# Si5351_STEMMA_QT_Schematic.net
KiCad netlist of a schematic drawn in EAGLE
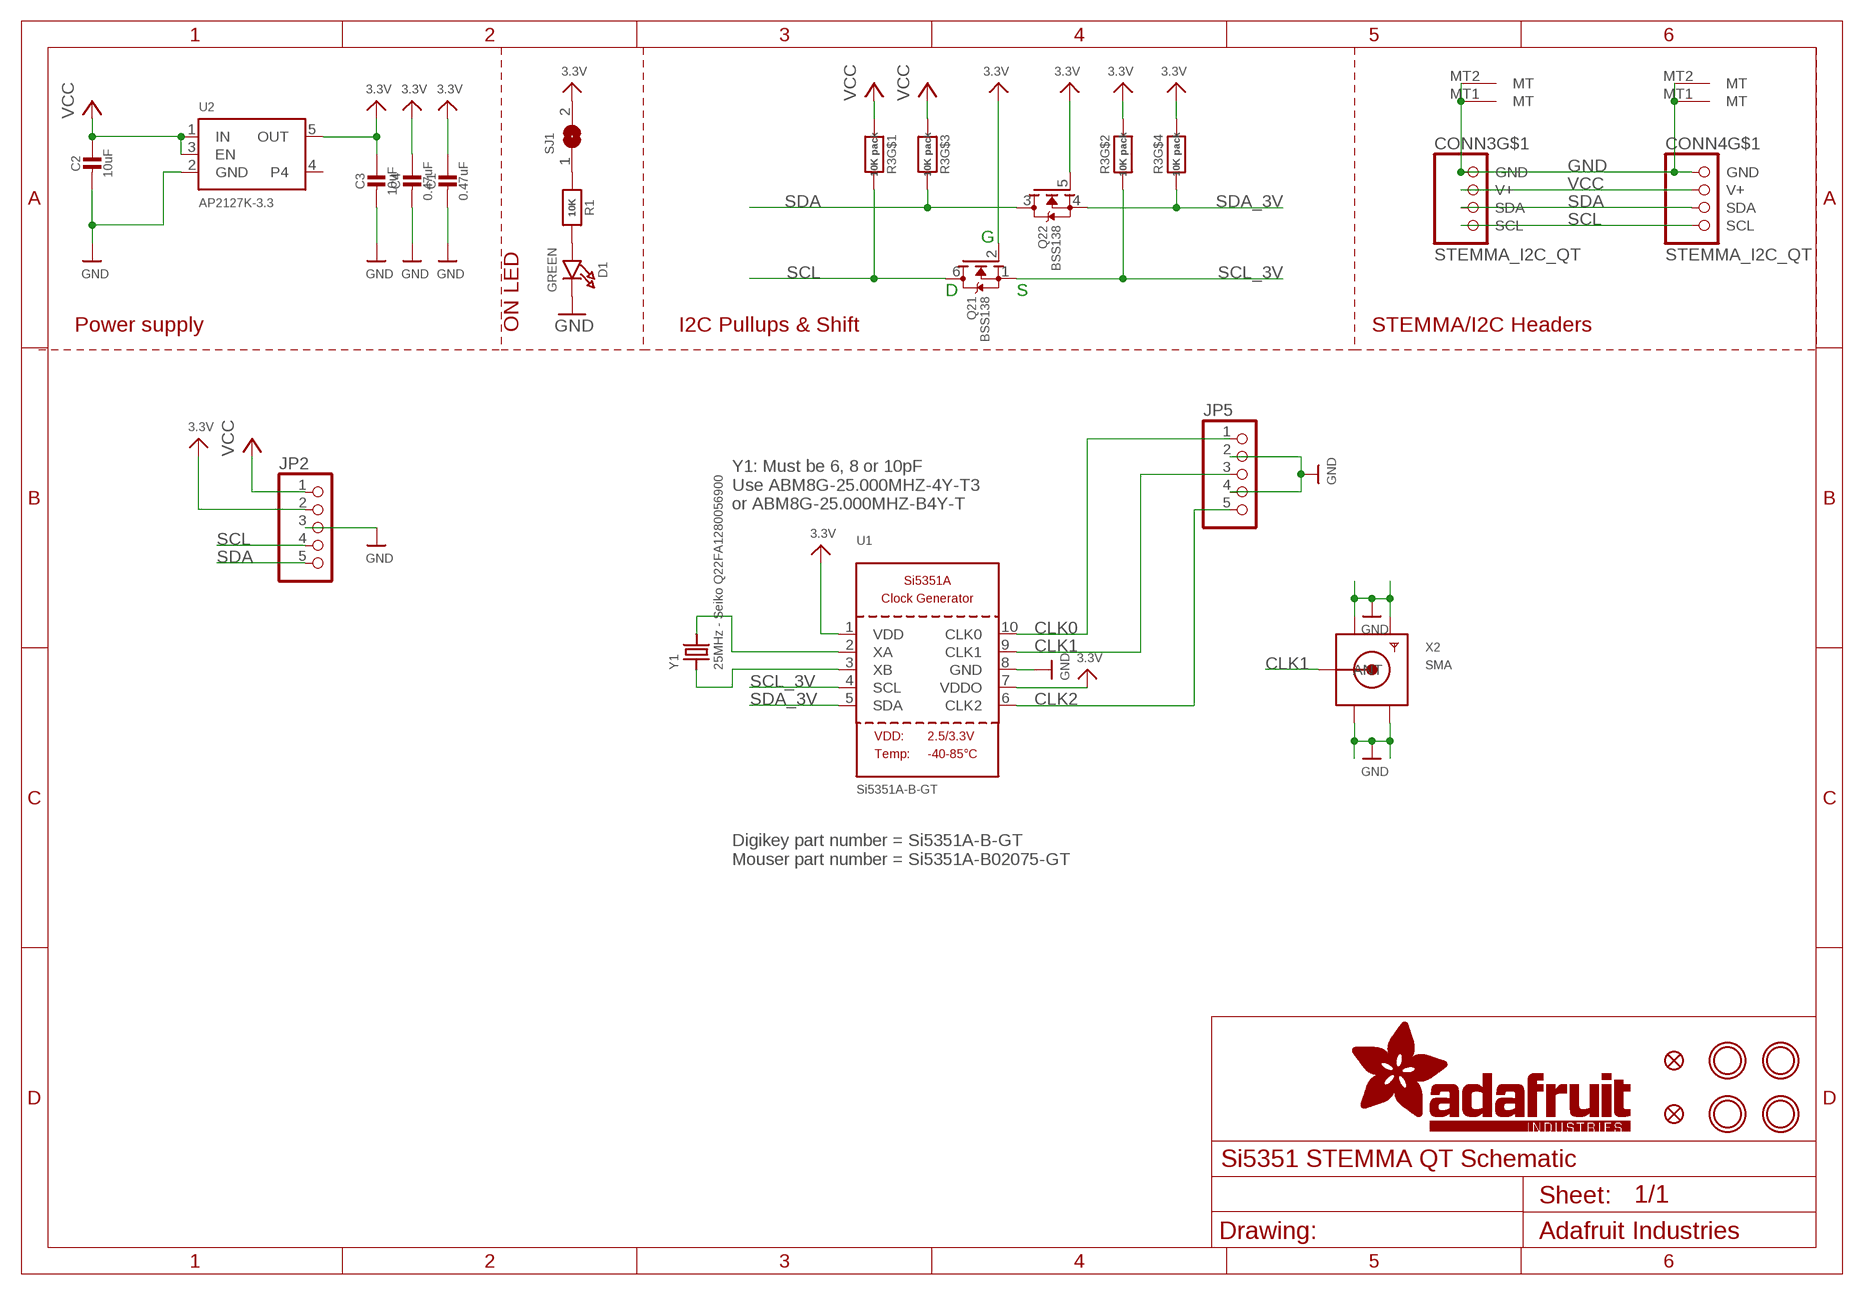
[diagram p0: schematic, sheet 1]

(export (version "E")
  (design (tool "Eeschema 10.0.6"))
  (components
    (comp (ref "C1")
      (value "0.47uF")
      (footprint "eagle-import:0603-NO")
      (libsource (lib "eagle-import") (part "CAP_CERAMIC0603_NO"))
    )
    (comp (ref "C2")
      (value "10uF")
      (footprint "eagle-import:0805-NO")
      (libsource (lib "eagle-import") (part "CAP_CERAMIC0805-NOOUTLINE"))
    )
    (comp (ref "C3")
      (value "10uF")
      (footprint "eagle-import:0805-NO")
      (libsource (lib "eagle-import") (part "CAP_CERAMIC0805-NOOUTLINE"))
    )
    (comp (ref "C4")
      (value "0.47uF")
      (footprint "eagle-import:0603-NO")
      (libsource (lib "eagle-import") (part "CAP_CERAMIC0603_NO"))
    )
    (comp (ref "CONN3")
      (value "STEMMA_I2C_QT")
      (footprint "eagle-import:JST_SH4")
      (libsource (lib "eagle-import") (part "STEMMA_I2C_QT"))
    )
    (comp (ref "CONN4")
      (value "STEMMA_I2C_QT")
      (footprint "eagle-import:JST_SH4")
      (libsource (lib "eagle-import") (part "STEMMA_I2C_QT"))
    )
    (comp (ref "D1")
      (value "GREEN")
      (footprint "eagle-import:CHIPLED_0603_NOOUTLINE")
      (libsource (lib "eagle-import") (part "LED0603_NOOUTLINE"))
    )
    (comp (ref "FID3")
      (value "FIDUCIAL_1MM")
      (footprint "eagle-import:FIDUCIAL_1MM")
      (libsource (lib "eagle-import") (part "FIDUCIAL_1MM"))
    )
    (comp (ref "FID4")
      (value "FIDUCIAL_1MM")
      (footprint "eagle-import:FIDUCIAL_1MM")
      (libsource (lib "eagle-import") (part "FIDUCIAL_1MM"))
    )
    (comp (ref "JP2")
      (value "HEADER-1X570MIL")
      (footprint "eagle-import:1X05_ROUND_70")
      (libsource (lib "eagle-import") (part "HEADER-1X570MIL"))
    )
    (comp (ref "JP5")
      (value "HEADER-1X570MIL")
      (footprint "eagle-import:1X05_ROUND_70")
      (libsource (lib "eagle-import") (part "HEADER-1X570MIL"))
    )
    (comp (ref "Q2")
      (value "BSS138")
      (footprint "eagle-import:SOT363")
      (libsource (lib "eagle-import") (part "MOSFET-N_DUAL"))
    )
    (comp (ref "R1")
      (value "10K")
      (footprint "eagle-import:0603-NO")
      (libsource (lib "eagle-import") (part "RESISTOR_0603_NOOUT"))
    )
    (comp (ref "R3")
      (value "10K pack")
      (footprint "eagle-import:RESPACK_4X0603")
      (libsource (lib "eagle-import") (part "RESISTOR_4PACK"))
    )
    (comp (ref "SJ1")
      (value "SOLDERJUMPERCLOSED")
      (footprint "eagle-import:SOLDERJUMPER_CLOSEDWIRE")
      (libsource (lib "eagle-import") (part "SOLDERJUMPERCLOSED"))
    )
    (comp (ref "U$1")
      (value "MOUNTINGHOLE2.5")
      (footprint "eagle-import:MOUNTINGHOLE_2.5_PLATED")
      (libsource (lib "eagle-import") (part "MOUNTINGHOLE2.5"))
    )
    (comp (ref "U$17")
      (value "MOUNTINGHOLE2.5")
      (footprint "eagle-import:MOUNTINGHOLE_2.5_PLATED")
      (libsource (lib "eagle-import") (part "MOUNTINGHOLE2.5"))
    )
    (comp (ref "U$19")
      (value "MOUNTINGHOLE2.5")
      (footprint "eagle-import:MOUNTINGHOLE_2.5_PLATED")
      (libsource (lib "eagle-import") (part "MOUNTINGHOLE2.5"))
    )
    (comp (ref "U$21")
      (value "MOUNTINGHOLE2.5")
      (footprint "eagle-import:MOUNTINGHOLE_2.5_PLATED")
      (libsource (lib "eagle-import") (part "MOUNTINGHOLE2.5"))
    )
    (comp (ref "U1")
      (value "Si5351A-B-GT")
      (footprint "eagle-import:MSOP10")
      (libsource (lib "eagle-import") (part "SI5351A"))
    )
    (comp (ref "U2")
      (value "AP2127K-3.3")
      (footprint "eagle-import:SOT23-5")
      (libsource (lib "eagle-import") (part "VREG_SOT23-5"))
    )
    (comp (ref "X2")
      (value "SMA")
      (footprint "eagle-import:SMA_EDGELAUNCH")
      (libsource (lib "eagle-import") (part "SMACONNECTOR_EDGE"))
    )
    (comp (ref "Y1")
      (value "25MHz - Seiko Q22FA1280056900")
      (footprint "eagle-import:CRYSTAL_2X1.6")
      (libsource (lib "eagle-import") (part "CRYSTAL_2X1.6MM"))
    )
  )
  (nets
    (net (code "1") (name "/CLK0") (class "Default")
      (node (ref "JP5") (pin "1") (pinfunction "1_1") (pintype "passive"))
      (node (ref "U1") (pin "10") (pinfunction "CLK0_10") (pintype "output"))
    )
    (net (code "2") (name "/CLK1") (class "Default")
      (node (ref "JP5") (pin "3") (pinfunction "3_3") (pintype "passive"))
      (node (ref "U1") (pin "9") (pinfunction "CLK1_9") (pintype "output"))
      (node (ref "X2") (pin "P") (pinfunction "ANT_P") (pintype "bidirectional"))
    )
    (net (code "3") (name "/CLK2") (class "Default")
      (node (ref "JP5") (pin "5") (pinfunction "5_5") (pintype "passive"))
      (node (ref "U1") (pin "6") (pinfunction "CLK2_6") (pintype "output"))
    )
    (net (code "4") (name "/SCL") (class "Default")
      (node (ref "CONN3") (pin "4") (pinfunction "SCL_4") (pintype "passive"))
      (node (ref "CONN4") (pin "4") (pinfunction "SCL_4") (pintype "passive"))
      (node (ref "JP2") (pin "4") (pinfunction "4_4") (pintype "passive"))
      (node (ref "Q2") (pin "6") (pinfunction "D_6") (pintype "bidirectional"))
      (node (ref "R3") (pin "8") (pinfunction "2_8") (pintype "passive"))
    )
    (net (code "5") (name "/SCL_3V") (class "Default")
      (node (ref "Q2") (pin "1") (pinfunction "S_1") (pintype "bidirectional"))
      (node (ref "R3") (pin "7") (pinfunction "2_7") (pintype "passive"))
      (node (ref "U1") (pin "4") (pinfunction "SCL_4") (pintype "input"))
    )
    (net (code "6") (name "/SDA") (class "Default")
      (node (ref "CONN3") (pin "3") (pinfunction "SDA_3") (pintype "passive"))
      (node (ref "CONN4") (pin "3") (pinfunction "SDA_3") (pintype "passive"))
      (node (ref "JP2") (pin "5") (pinfunction "5_5") (pintype "passive"))
      (node (ref "Q2") (pin "3") (pinfunction "D_3") (pintype "bidirectional"))
      (node (ref "R3") (pin "6") (pinfunction "2_6") (pintype "passive"))
    )
    (net (code "7") (name "/SDA_3V") (class "Default")
      (node (ref "Q2") (pin "4") (pinfunction "S_4") (pintype "bidirectional"))
      (node (ref "R3") (pin "5") (pinfunction "2_5") (pintype "passive"))
      (node (ref "U1") (pin "5") (pinfunction "SDA_5") (pintype "bidirectional"))
    )
    (net (code "8") (name "3.3V") (class "Default")
      (node (ref "C1") (pin "1") (pinfunction "1_1") (pintype "passive"))
      (node (ref "C3") (pin "1") (pinfunction "1_1") (pintype "passive"))
      (node (ref "C4") (pin "1") (pinfunction "1_1") (pintype "passive"))
      (node (ref "JP2") (pin "2") (pinfunction "2_2") (pintype "passive"))
      (node (ref "Q2") (pin "2") (pinfunction "G_2") (pintype "bidirectional"))
      (node (ref "Q2") (pin "5") (pinfunction "G_5") (pintype "bidirectional"))
      (node (ref "R3") (pin "2") (pinfunction "1_2") (pintype "passive"))
      (node (ref "R3") (pin "4") (pinfunction "1_4") (pintype "passive"))
      (node (ref "SJ1") (pin "2") (pinfunction "2_2") (pintype "passive"))
      (node (ref "U1") (pin "1") (pinfunction "VDD_1") (pintype "power_in"))
      (node (ref "U1") (pin "7") (pinfunction "VDDO_7") (pintype "power_in"))
      (node (ref "U2") (pin "5") (pinfunction "OUT_5") (pintype "power_in"))
    )
    (net (code "9") (name "GND") (class "Default")
      (node (ref "C1") (pin "2") (pinfunction "2_2") (pintype "passive"))
      (node (ref "C2") (pin "2") (pinfunction "2_2") (pintype "passive"))
      (node (ref "C3") (pin "2") (pinfunction "2_2") (pintype "passive"))
      (node (ref "C4") (pin "2") (pinfunction "2_2") (pintype "passive"))
      (node (ref "CONN3") (pin "1") (pinfunction "GND_1") (pintype "passive"))
      (node (ref "CONN3") (pin "MT1") (pinfunction "MT_MT1") (pintype "bidirectional"))
      (node (ref "CONN3") (pin "MT2") (pinfunction "MT_MT2") (pintype "bidirectional"))
      (node (ref "CONN4") (pin "1") (pinfunction "GND_1") (pintype "passive"))
      (node (ref "CONN4") (pin "MT1") (pinfunction "MT_MT1") (pintype "bidirectional"))
      (node (ref "CONN4") (pin "MT2") (pinfunction "MT_MT2") (pintype "bidirectional"))
      (node (ref "D1") (pin "C") (pinfunction "C_C") (pintype "passive"))
      (node (ref "JP2") (pin "3") (pinfunction "3_3") (pintype "passive"))
      (node (ref "JP5") (pin "2") (pinfunction "2_2") (pintype "passive"))
      (node (ref "JP5") (pin "4") (pinfunction "4_4") (pintype "passive"))
      (node (ref "U1") (pin "8") (pinfunction "GND_8") (pintype "power_in"))
      (node (ref "U2") (pin "2") (pinfunction "GND_2") (pintype "power_in"))
      (node (ref "X2") (pin "GND@1") (pinfunction "GND4_GND@1") (pintype "power_in"))
      (node (ref "X2") (pin "GND@2") (pinfunction "GND3_GND@2") (pintype "power_in"))
      (node (ref "X2") (pin "GND@3") (pinfunction "GND2_GND@3") (pintype "power_in"))
      (node (ref "X2") (pin "GND@4") (pinfunction "GND1_GND@4") (pintype "power_in"))
    )
    (net (code "10") (name "Net-(D1-PadA)") (class "Default")
      (node (ref "D1") (pin "A") (pinfunction "A_A") (pintype "passive"))
      (node (ref "R1") (pin "2") (pinfunction "2_2") (pintype "passive"))
    )
    (net (code "11") (name "Net-(R1-Pad1)") (class "Default")
      (node (ref "R1") (pin "1") (pinfunction "1_1") (pintype "passive"))
      (node (ref "SJ1") (pin "1") (pinfunction "1_1") (pintype "passive"))
    )
    (net (code "12") (name "Net-(U1-XA)") (class "Default")
      (node (ref "U1") (pin "2") (pinfunction "XA_2") (pintype "input"))
      (node (ref "Y1") (pin "3") (pinfunction "2_3") (pintype "passive"))
    )
    (net (code "13") (name "Net-(U1-XB)") (class "Default")
      (node (ref "U1") (pin "3") (pinfunction "XB_3") (pintype "input"))
      (node (ref "Y1") (pin "1") (pinfunction "1_1") (pintype "passive"))
    )
    (net (code "14") (name "VCC") (class "Default")
      (node (ref "C2") (pin "1") (pinfunction "1_1") (pintype "passive"))
      (node (ref "CONN3") (pin "2") (pinfunction "V+_2") (pintype "passive"))
      (node (ref "CONN4") (pin "2") (pinfunction "V+_2") (pintype "passive"))
      (node (ref "JP2") (pin "1") (pinfunction "1_1") (pintype "passive"))
      (node (ref "R3") (pin "1") (pinfunction "1_1") (pintype "passive"))
      (node (ref "R3") (pin "3") (pinfunction "1_3") (pintype "passive"))
      (node (ref "U2") (pin "1") (pinfunction "IN_1") (pintype "power_in"))
      (node (ref "U2") (pin "3") (pinfunction "EN_3") (pintype "input"))
    )
    (net (code "15") (name "unconnected-(U2-P4-Pad4)") (class "Default")
      (node (ref "U2") (pin "4") (pinfunction "P4_4") (pintype "bidirectional"))
    )
  )
)
